# pix-diff-spi-v1a.net
KiCad netlist of a schematic drawn in EAGLE
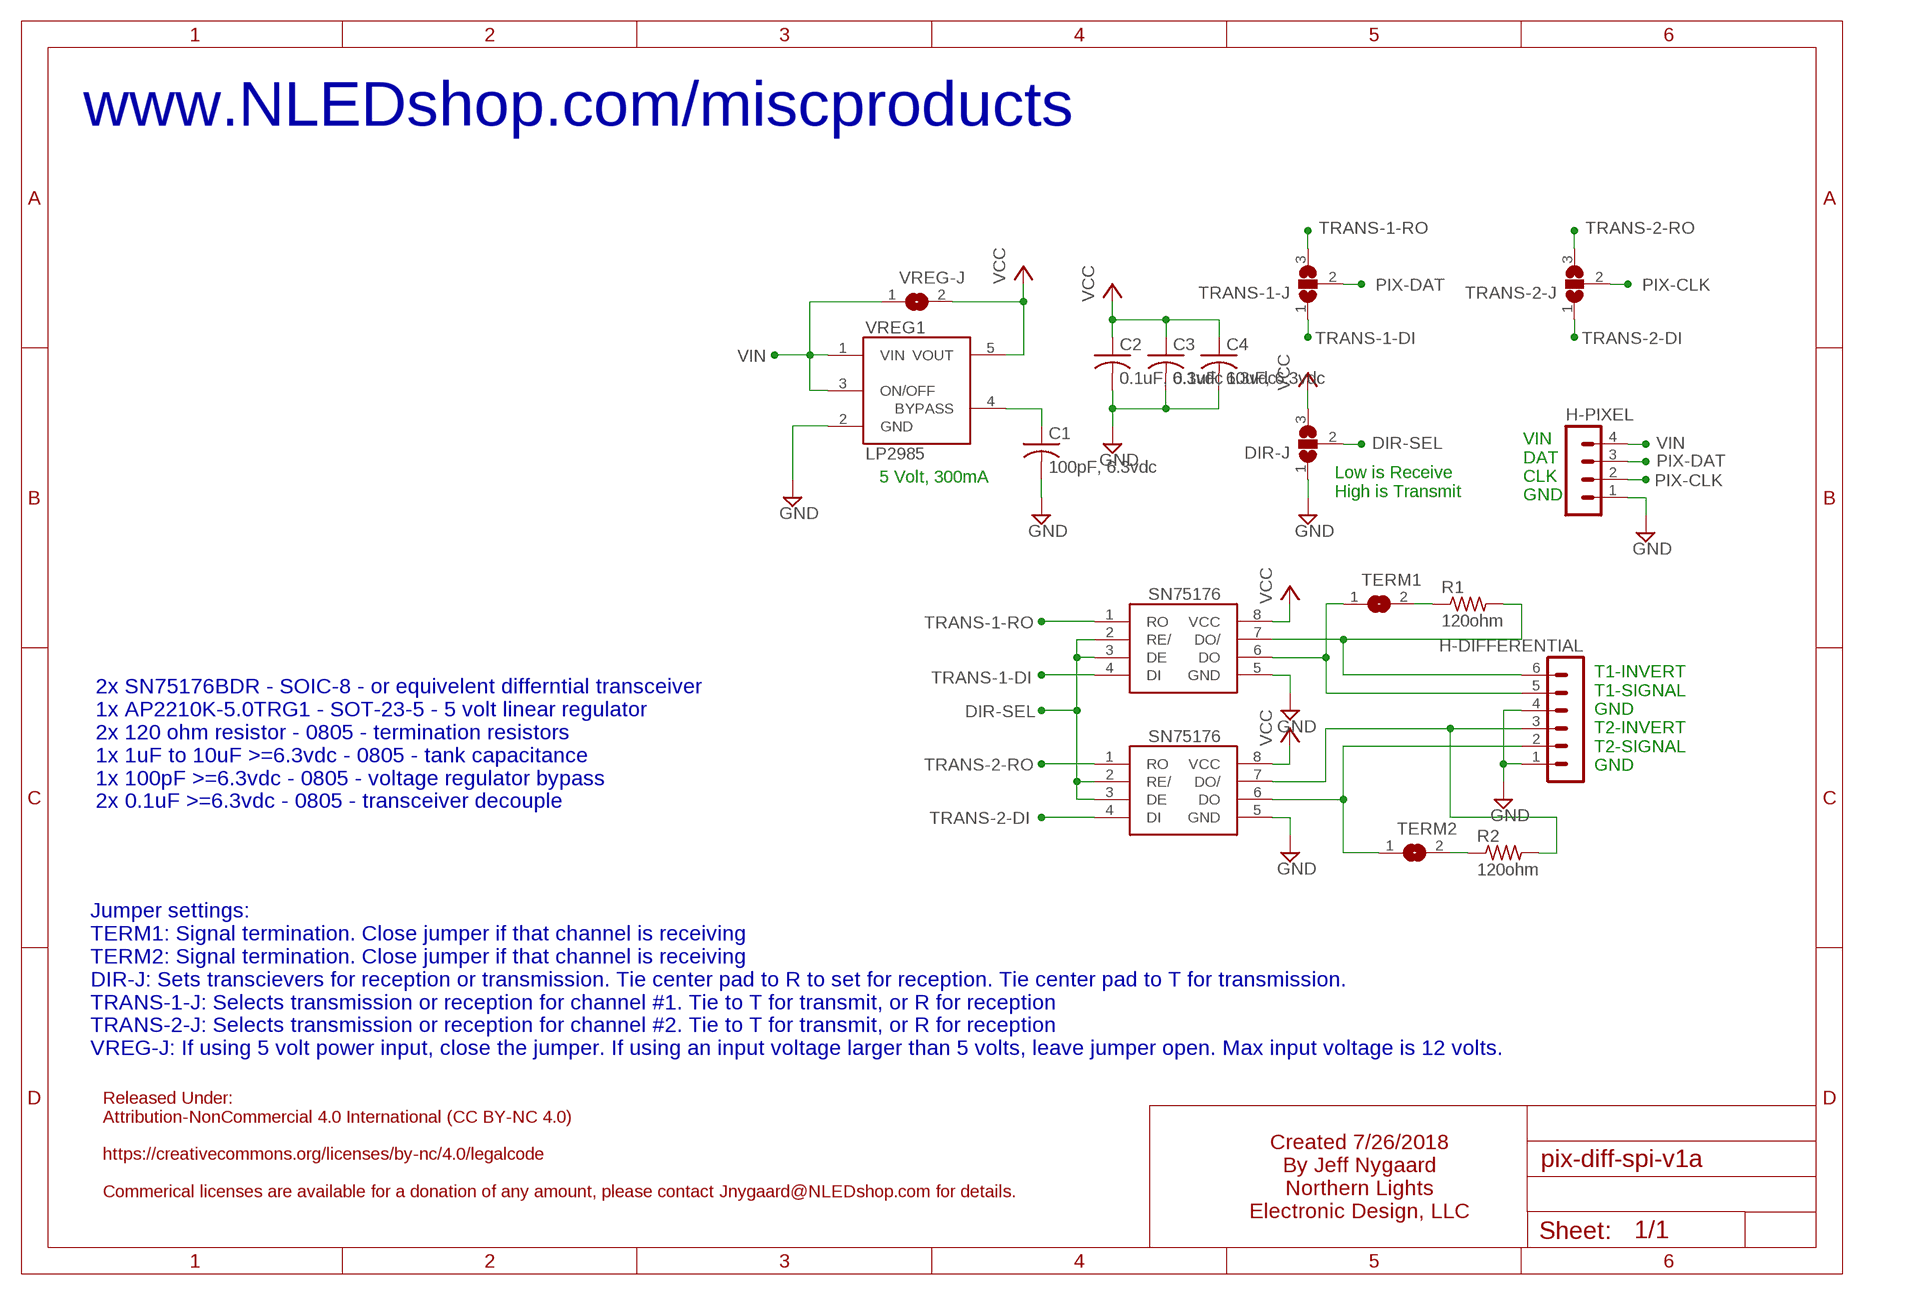
[diagram p0: schematic, sheet 1]

(export (version "E")
  (design (tool "Eeschema 10.0.6"))
  (components
    (comp (ref "C1")
      (value "100pF, 6.3vdc")
      (footprint "eagle-import:C0805")
      (libsource (lib "eagle-import") (part "C-USC0805"))
    )
    (comp (ref "C2")
      (value "0.1uF, 6.3vdc")
      (footprint "eagle-import:C0805")
      (libsource (lib "eagle-import") (part "C-USC0805"))
    )
    (comp (ref "C3")
      (value "0.1uF, 6.3vdc")
      (footprint "eagle-import:C0805")
      (libsource (lib "eagle-import") (part "C-USC0805"))
    )
    (comp (ref "C4")
      (value "10uF, 6.3vdc")
      (footprint "eagle-import:C0805")
      (libsource (lib "eagle-import") (part "C-USC0805"))
    )
    (comp (ref "DIR-J")
      (value "SJ2W")
      (footprint "eagle-import:SJ_2")
      (libsource (lib "eagle-import") (part "SJ2W"))
    )
    (comp (ref "H-DIFFERENTIAL")
      (value "MA06-1")
      (footprint "eagle-import:MA06-1")
      (libsource (lib "eagle-import") (part "MA06-1"))
    )
    (comp (ref "H-PIXEL")
      (value "MA04-1")
      (footprint "eagle-import:MA04-1")
      (libsource (lib "eagle-import") (part "MA04-1"))
    )
    (comp (ref "R1")
      (value "120ohm")
      (footprint "eagle-import:R0805")
      (libsource (lib "eagle-import") (part "R-US_R0805"))
    )
    (comp (ref "R2")
      (value "120ohm")
      (footprint "eagle-import:R0805")
      (libsource (lib "eagle-import") (part "R-US_R0805"))
    )
    (comp (ref "TERM1")
      (value "SJ")
      (footprint "eagle-import:SJ")
      (libsource (lib "eagle-import") (part "SJ"))
    )
    (comp (ref "TERM2")
      (value "SJ")
      (footprint "eagle-import:SJ")
      (libsource (lib "eagle-import") (part "SJ"))
    )
    (comp (ref "TRANS-1-J")
      (value "SJ2W")
      (footprint "eagle-import:SJ_2")
      (libsource (lib "eagle-import") (part "SJ2W"))
    )
    (comp (ref "TRANS-2-J")
      (value "SJ2W")
      (footprint "eagle-import:SJ_2")
      (libsource (lib "eagle-import") (part "SJ2W"))
    )
    (comp (ref "TRANS1")
      (value "SN75176SMD")
      (footprint "eagle-import:SOIC-8")
      (libsource (lib "eagle-import") (part "SN75176SMD"))
    )
    (comp (ref "TRANS2")
      (value "SN75176SMD")
      (footprint "eagle-import:SOIC-8")
      (libsource (lib "eagle-import") (part "SN75176SMD"))
    )
    (comp (ref "VREG-J")
      (value "SJ")
      (footprint "eagle-import:SJ")
      (libsource (lib "eagle-import") (part "SJ"))
    )
    (comp (ref "VREG1")
      (value "LP2985AIM5-3.3")
      (footprint "eagle-import:SOT25")
      (libsource (lib "eagle-import") (part "LP2985AIM5-3.3"))
    )
  )
  (nets
    (net (code "1") (name "/DIR-SEL") (class "Default")
      (node (ref "DIR-J") (pin "2") (pinfunction "2_2") (pintype "passive"))
      (node (ref "TRANS1") (pin "2") (pinfunction "RE/_2") (pintype "bidirectional"))
      (node (ref "TRANS1") (pin "3") (pinfunction "DE_3") (pintype "bidirectional"))
      (node (ref "TRANS2") (pin "2") (pinfunction "RE/_2") (pintype "bidirectional"))
      (node (ref "TRANS2") (pin "3") (pinfunction "DE_3") (pintype "bidirectional"))
    )
    (net (code "2") (name "/PIX-CLK") (class "Default")
      (node (ref "H-PIXEL") (pin "2") (pinfunction "2_2") (pintype "passive"))
      (node (ref "TRANS-2-J") (pin "2") (pinfunction "2_2") (pintype "passive"))
    )
    (net (code "3") (name "/PIX-DAT") (class "Default")
      (node (ref "H-PIXEL") (pin "3") (pinfunction "3_3") (pintype "passive"))
      (node (ref "TRANS-1-J") (pin "2") (pinfunction "2_2") (pintype "passive"))
    )
    (net (code "4") (name "/TRANS-1-DI") (class "Default")
      (node (ref "TRANS-1-J") (pin "1") (pinfunction "1_1") (pintype "passive"))
      (node (ref "TRANS1") (pin "4") (pinfunction "DI_4") (pintype "bidirectional"))
    )
    (net (code "5") (name "/TRANS-1-RO") (class "Default")
      (node (ref "TRANS-1-J") (pin "3") (pinfunction "3_3") (pintype "passive"))
      (node (ref "TRANS1") (pin "1") (pinfunction "RO_1") (pintype "bidirectional"))
    )
    (net (code "6") (name "/TRANS-2-DI") (class "Default")
      (node (ref "TRANS-2-J") (pin "1") (pinfunction "1_1") (pintype "passive"))
      (node (ref "TRANS2") (pin "4") (pinfunction "DI_4") (pintype "bidirectional"))
    )
    (net (code "7") (name "/TRANS-2-RO") (class "Default")
      (node (ref "TRANS-2-J") (pin "3") (pinfunction "3_3") (pintype "passive"))
      (node (ref "TRANS2") (pin "1") (pinfunction "RO_1") (pintype "bidirectional"))
    )
    (net (code "8") (name "/VIN") (class "Default")
      (node (ref "H-PIXEL") (pin "4") (pinfunction "4_4") (pintype "passive"))
      (node (ref "VREG-J") (pin "1") (pinfunction "1_1") (pintype "passive"))
      (node (ref "VREG1") (pin "1") (pinfunction "VIN_1") (pintype "power_in"))
      (node (ref "VREG1") (pin "3") (pinfunction "ON/OFF_3") (pintype "input"))
    )
    (net (code "9") (name "GND") (class "Default")
      (node (ref "C1") (pin "2") (pinfunction "2_2") (pintype "passive"))
      (node (ref "C2") (pin "2") (pinfunction "2_2") (pintype "passive"))
      (node (ref "C3") (pin "2") (pinfunction "2_2") (pintype "passive"))
      (node (ref "C4") (pin "2") (pinfunction "2_2") (pintype "passive"))
      (node (ref "DIR-J") (pin "1") (pinfunction "1_1") (pintype "passive"))
      (node (ref "H-DIFFERENTIAL") (pin "1") (pinfunction "1_1") (pintype "passive"))
      (node (ref "H-DIFFERENTIAL") (pin "4") (pinfunction "4_4") (pintype "passive"))
      (node (ref "H-PIXEL") (pin "1") (pinfunction "1_1") (pintype "passive"))
      (node (ref "TRANS1") (pin "5") (pinfunction "GND_5") (pintype "bidirectional"))
      (node (ref "TRANS2") (pin "5") (pinfunction "GND_5") (pintype "bidirectional"))
      (node (ref "VREG1") (pin "2") (pinfunction "GND_2") (pintype "power_in"))
    )
    (net (code "10") (name "Net-(R1-Pad1)") (class "Default")
      (node (ref "R1") (pin "1") (pinfunction "1_1") (pintype "passive"))
      (node (ref "TERM1") (pin "2") (pinfunction "2_2") (pintype "passive"))
    )
    (net (code "11") (name "Net-(R2-Pad1)") (class "Default")
      (node (ref "R2") (pin "1") (pinfunction "1_1") (pintype "passive"))
      (node (ref "TERM2") (pin "2") (pinfunction "2_2") (pintype "passive"))
    )
    (net (code "12") (name "Net-(TRANS1-DO)") (class "Default")
      (node (ref "H-DIFFERENTIAL") (pin "5") (pinfunction "5_5") (pintype "passive"))
      (node (ref "TERM1") (pin "1") (pinfunction "1_1") (pintype "passive"))
      (node (ref "TRANS1") (pin "6") (pinfunction "DO_6") (pintype "bidirectional"))
    )
    (net (code "13") (name "Net-(TRANS1-DO{slash})") (class "Default")
      (node (ref "H-DIFFERENTIAL") (pin "6") (pinfunction "6_6") (pintype "passive"))
      (node (ref "R1") (pin "2") (pinfunction "2_2") (pintype "passive"))
      (node (ref "TRANS1") (pin "7") (pinfunction "DO/_7") (pintype "bidirectional"))
    )
    (net (code "14") (name "Net-(TRANS2-DO)") (class "Default")
      (node (ref "H-DIFFERENTIAL") (pin "2") (pinfunction "2_2") (pintype "passive"))
      (node (ref "TERM2") (pin "1") (pinfunction "1_1") (pintype "passive"))
      (node (ref "TRANS2") (pin "6") (pinfunction "DO_6") (pintype "bidirectional"))
    )
    (net (code "15") (name "Net-(TRANS2-DO{slash})") (class "Default")
      (node (ref "H-DIFFERENTIAL") (pin "3") (pinfunction "3_3") (pintype "passive"))
      (node (ref "R2") (pin "2") (pinfunction "2_2") (pintype "passive"))
      (node (ref "TRANS2") (pin "7") (pinfunction "DO/_7") (pintype "bidirectional"))
    )
    (net (code "16") (name "Net-(VREG1-BYPASS)") (class "Default")
      (node (ref "C1") (pin "1") (pinfunction "1_1") (pintype "passive"))
      (node (ref "VREG1") (pin "4") (pinfunction "BYPASS_4") (pintype "power_in"))
    )
    (net (code "17") (name "VCC") (class "Default")
      (node (ref "C2") (pin "1") (pinfunction "1_1") (pintype "passive"))
      (node (ref "C3") (pin "1") (pinfunction "1_1") (pintype "passive"))
      (node (ref "C4") (pin "1") (pinfunction "1_1") (pintype "passive"))
      (node (ref "DIR-J") (pin "3") (pinfunction "3_3") (pintype "passive"))
      (node (ref "TRANS1") (pin "8") (pinfunction "VCC_8") (pintype "bidirectional"))
      (node (ref "TRANS2") (pin "8") (pinfunction "VCC_8") (pintype "bidirectional"))
      (node (ref "VREG-J") (pin "2") (pinfunction "2_2") (pintype "passive"))
      (node (ref "VREG1") (pin "5") (pinfunction "VOUT_5") (pintype "power_in"))
    )
  )
)
